# alps_adapter.net
KiCad netlist of a schematic drawn in Altium Designer
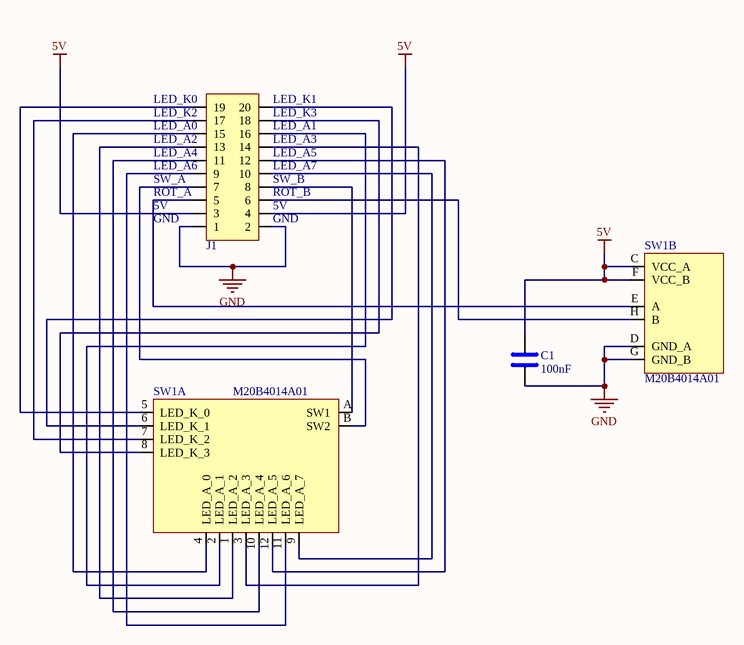
[diagram p0: alps_adapter.SchDoc]

(export (version "E")
  (design (tool "Eeschema 10.0.6"))
  (components
    (comp (ref "C1")
      (value "100nF")
      (footprint "0805")
      (description "100nF 50V MLCC 0805")
      (fields (field (name "VOLTAGE") "50V"))
      (libsource (lib "capacitors") (part "100nF 50V MLCC 0805"))
    )
    (comp (ref "J1")
      (value "Wannenstecker 20pol 2,54mm")
      (footprint "WSL20G")
      (libsource (lib "wannenstecker") (part "Wannenstecker 20pol 2,54mm"))
    )
    (comp (ref "SW1")
      (value "M20B4014A01")
      (footprint "ALPS_EM20B4014A01-LED")
      (description "ALPS magnetic rotary encoder with leds")
      (libsource (lib "switch_relais") (part "ALPS_EM20B4014A01-LED"))
    )
  )
  (nets
    (net (code "1") (name "5V") (class "Default")
      (node (ref "C1") (pin "1") (pinfunction "1_1") (pintype "passive"))
      (node (ref "J1") (pin "3") (pinfunction "3_3") (pintype "passive"))
      (node (ref "J1") (pin "4") (pinfunction "4_4") (pintype "passive"))
      (node (ref "SW1") (pin "C") (pinfunction "VCC_A_C") (pintype "passive"))
      (node (ref "SW1") (pin "F") (pinfunction "VCC_B_F") (pintype "passive"))
    )
    (net (code "2") (name "GND") (class "Default")
      (node (ref "C1") (pin "2") (pinfunction "2_2") (pintype "passive"))
      (node (ref "J1") (pin "1") (pinfunction "1_1") (pintype "passive"))
      (node (ref "J1") (pin "2") (pinfunction "2_2") (pintype "passive"))
      (node (ref "SW1") (pin "D") (pinfunction "GND_A_D") (pintype "passive"))
      (node (ref "SW1") (pin "G") (pinfunction "GND_B_G") (pintype "passive"))
    )
    (net (code "3") (name "Net-(SW1A-LED_A_0)") (class "Default")
      (node (ref "J1") (pin "15") (pinfunction "15_15") (pintype "passive"))
      (node (ref "SW1") (pin "4") (pinfunction "LED_A_0_4") (pintype "passive"))
    )
    (net (code "4") (name "Net-(SW1A-LED_A_1)") (class "Default")
      (node (ref "J1") (pin "16") (pinfunction "16_16") (pintype "passive"))
      (node (ref "SW1") (pin "2") (pinfunction "LED_A_1_2") (pintype "passive"))
    )
    (net (code "5") (name "Net-(SW1A-LED_A_2)") (class "Default")
      (node (ref "J1") (pin "13") (pinfunction "13_13") (pintype "passive"))
      (node (ref "SW1") (pin "1") (pinfunction "LED_A_2_1") (pintype "passive"))
    )
    (net (code "6") (name "Net-(SW1A-LED_A_3)") (class "Default")
      (node (ref "J1") (pin "14") (pinfunction "14_14") (pintype "passive"))
      (node (ref "SW1") (pin "3") (pinfunction "LED_A_3_3") (pintype "passive"))
    )
    (net (code "7") (name "Net-(SW1A-LED_A_4)") (class "Default")
      (node (ref "J1") (pin "11") (pinfunction "11_11") (pintype "passive"))
      (node (ref "SW1") (pin "10") (pinfunction "LED_A_4_10") (pintype "passive"))
    )
    (net (code "8") (name "Net-(SW1A-LED_A_5)") (class "Default")
      (node (ref "J1") (pin "12") (pinfunction "12_12") (pintype "passive"))
      (node (ref "SW1") (pin "12") (pinfunction "LED_A_5_12") (pintype "passive"))
    )
    (net (code "9") (name "Net-(SW1A-LED_A_6)") (class "Default")
      (node (ref "J1") (pin "9") (pinfunction "9_9") (pintype "passive"))
      (node (ref "SW1") (pin "11") (pinfunction "LED_A_6_11") (pintype "passive"))
    )
    (net (code "10") (name "Net-(SW1A-LED_A_7)") (class "Default")
      (node (ref "J1") (pin "10") (pinfunction "10_10") (pintype "passive"))
      (node (ref "SW1") (pin "9") (pinfunction "LED_A_7_9") (pintype "passive"))
    )
    (net (code "11") (name "Net-(SW1A-LED_K_0)") (class "Default")
      (node (ref "J1") (pin "19") (pinfunction "19_19") (pintype "passive"))
      (node (ref "SW1") (pin "5") (pinfunction "LED_K_0_5") (pintype "passive"))
    )
    (net (code "12") (name "Net-(SW1A-LED_K_1)") (class "Default")
      (node (ref "J1") (pin "20") (pinfunction "20_20") (pintype "passive"))
      (node (ref "SW1") (pin "6") (pinfunction "LED_K_1_6") (pintype "passive"))
    )
    (net (code "13") (name "Net-(SW1A-LED_K_2)") (class "Default")
      (node (ref "J1") (pin "17") (pinfunction "17_17") (pintype "passive"))
      (node (ref "SW1") (pin "7") (pinfunction "LED_K_2_7") (pintype "passive"))
    )
    (net (code "14") (name "Net-(SW1A-LED_K_3)") (class "Default")
      (node (ref "J1") (pin "18") (pinfunction "18_18") (pintype "passive"))
      (node (ref "SW1") (pin "8") (pinfunction "LED_K_3_8") (pintype "passive"))
    )
    (net (code "15") (name "Net-(SW1A-SW1)") (class "Default")
      (node (ref "J1") (pin "8") (pinfunction "8_8") (pintype "passive"))
      (node (ref "SW1") (pin "A") (pinfunction "SW1_A") (pintype "passive"))
    )
    (net (code "16") (name "Net-(SW1A-SW2)") (class "Default")
      (node (ref "J1") (pin "7") (pinfunction "7_7") (pintype "passive"))
      (node (ref "SW1") (pin "B") (pinfunction "SW2_B") (pintype "passive"))
    )
    (net (code "17") (name "Net-(SW1B-A)") (class "Default")
      (node (ref "J1") (pin "5") (pinfunction "5_5") (pintype "passive"))
      (node (ref "SW1") (pin "E") (pinfunction "A_E") (pintype "passive"))
    )
    (net (code "18") (name "Net-(SW1B-B)") (class "Default")
      (node (ref "J1") (pin "6") (pinfunction "6_6") (pintype "passive"))
      (node (ref "SW1") (pin "H") (pinfunction "B_H") (pintype "passive"))
    )
  )
)
